# ThermoBot.net
KiCad netlist of a schematic drawn in EAGLE
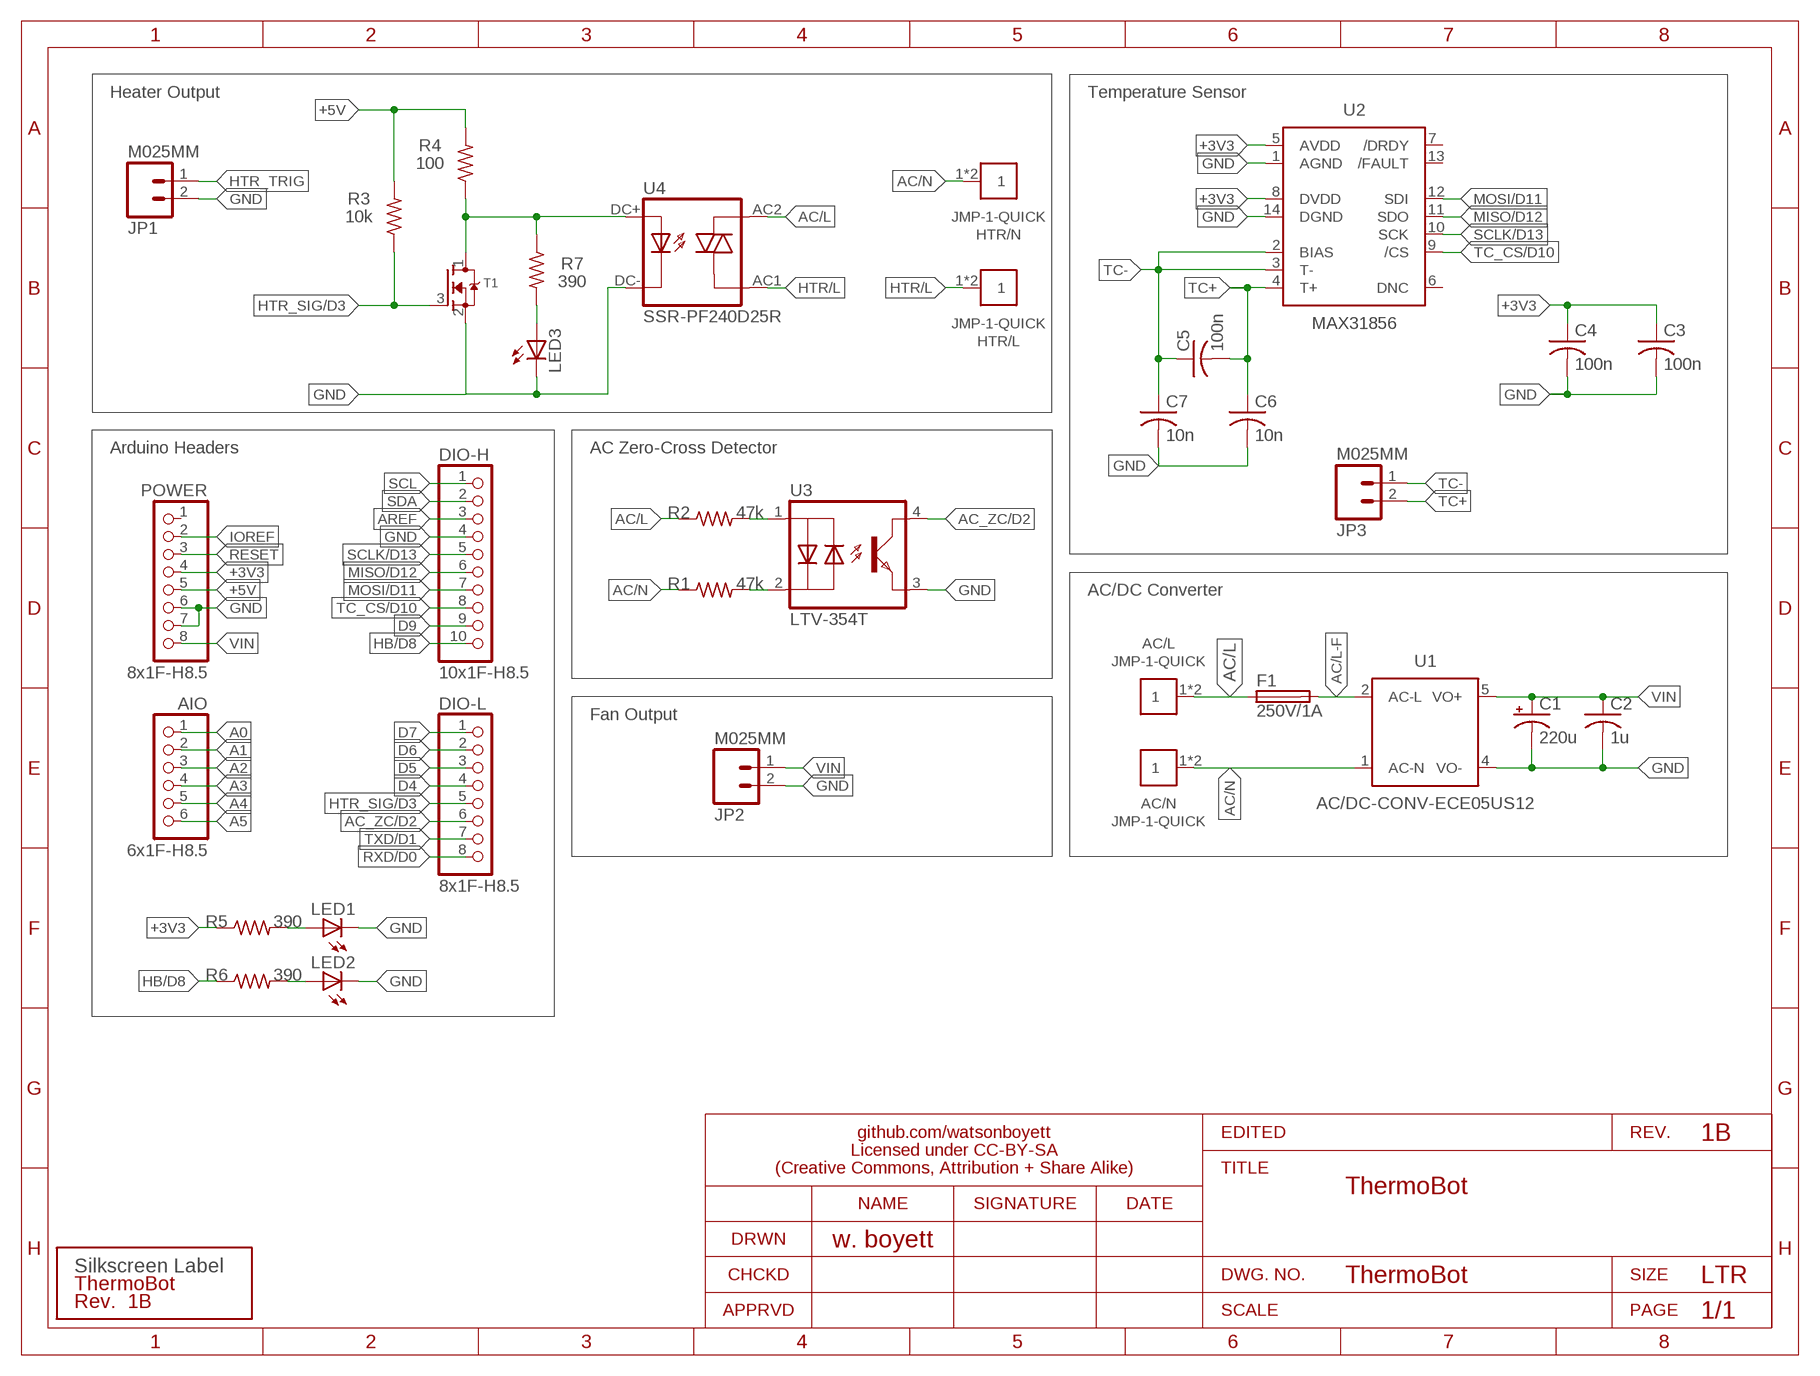
[diagram p0: schematic, sheet 1]

(export (version "E")
  (design (tool "Eeschema 10.0.6"))
  (components
    (comp (ref "AC/L")
      (value "JMP-1-QUICK")
      (footprint "eagle-import:QUICK-1")
      (fields (field (name "MPN") "1287"))
      (libsource (lib "eagle-import") (part "JMP-1-QUICK"))
    )
    (comp (ref "AC/N")
      (value "JMP-1-QUICK")
      (footprint "eagle-import:QUICK-1")
      (fields (field (name "MPN") "1287"))
      (libsource (lib "eagle-import") (part "JMP-1-QUICK"))
    )
    (comp (ref "AIO")
      (value "6x1F-H8.5")
      (footprint "eagle-import:1X06")
      (libsource (lib "eagle-import") (part "PINHD-1X6TH"))
    )
    (comp (ref "C1")
      (value "220u")
      (footprint "eagle-import:153CLV-1014")
      (libsource (lib "eagle-import") (part "CPOL-US153CLV-1014"))
    )
    (comp (ref "C2")
      (value "1u")
      (footprint "eagle-import:C0805")
      (libsource (lib "eagle-import") (part "C-USC0805"))
    )
    (comp (ref "C3")
      (value "100n")
      (footprint "eagle-import:C0805")
      (libsource (lib "eagle-import") (part "C-USC0805"))
    )
    (comp (ref "C4")
      (value "100n")
      (footprint "eagle-import:C0805")
      (libsource (lib "eagle-import") (part "C-USC0805"))
    )
    (comp (ref "C5")
      (value "100n")
      (footprint "eagle-import:C0805")
      (libsource (lib "eagle-import") (part "C-USC0805"))
    )
    (comp (ref "C6")
      (value "10n")
      (footprint "eagle-import:C0805")
      (libsource (lib "eagle-import") (part "C-USC0805"))
    )
    (comp (ref "C7")
      (value "10n")
      (footprint "eagle-import:C0805")
      (libsource (lib "eagle-import") (part "C-USC0805"))
    )
    (comp (ref "DIO-H")
      (value "10x1F-H8.5")
      (footprint "eagle-import:1X10")
      (libsource (lib "eagle-import") (part "PINHD-1X10TH"))
    )
    (comp (ref "DIO-L")
      (value "8x1F-H8.5")
      (footprint "eagle-import:1X08")
      (libsource (lib "eagle-import") (part "PINHD-1X8TH"))
    )
    (comp (ref "F1")
      (value "250V/1A")
      (footprint "eagle-import:2SMD-2410")
      (fields
        (field (name "MPN") "0452004.MRL")
        (field (name "MPN_1") "0454001.MR")
        (field (name "PN-DK") "F3144CT-ND")
      )
      (libsource (lib "eagle-import") (part "FUSE2410"))
    )
    (comp (ref "HTR/L")
      (value "JMP-1-QUICK")
      (footprint "eagle-import:QUICK-1")
      (fields (field (name "MPN") "1287"))
      (libsource (lib "eagle-import") (part "JMP-1-QUICK"))
    )
    (comp (ref "HTR/N")
      (value "JMP-1-QUICK")
      (footprint "eagle-import:QUICK-1")
      (fields (field (name "MPN") "1287"))
      (libsource (lib "eagle-import") (part "JMP-1-QUICK"))
    )
    (comp (ref "JP1")
      (value "M025MM")
      (footprint "eagle-import:SCREWTERMINAL-5MM-2")
      (fields (field (name "MPN") "1729128"))
      (libsource (lib "eagle-import") (part "M025MM"))
    )
    (comp (ref "JP2")
      (value "M025MM")
      (footprint "eagle-import:SCREWTERMINAL-5MM-2")
      (fields (field (name "MPN") "1729128"))
      (libsource (lib "eagle-import") (part "M025MM"))
    )
    (comp (ref "JP3")
      (value "M025MM")
      (footprint "eagle-import:SCREWTERMINAL-5MM-2")
      (fields (field (name "MPN") "1729128"))
      (libsource (lib "eagle-import") (part "M025MM"))
    )
    (comp (ref "LED1")
      (value "LEDCHIP-LED0805")
      (footprint "eagle-import:CHIP-LED0805")
      (fields (field (name "MPN") "SML-LXT0805IW-TR"))
      (libsource (lib "eagle-import") (part "LEDCHIP-LED0805"))
    )
    (comp (ref "LED2")
      (value "LEDCHIP-LED0805")
      (footprint "eagle-import:CHIP-LED0805")
      (fields (field (name "MPN") "SML-LXT0805IW-TR"))
      (libsource (lib "eagle-import") (part "LEDCHIP-LED0805"))
    )
    (comp (ref "LED3")
      (value "LEDCHIP-LED0805")
      (footprint "eagle-import:CHIP-LED0805")
      (fields (field (name "MPN") "SML-LXT0805IW-TR"))
      (libsource (lib "eagle-import") (part "LEDCHIP-LED0805"))
    )
    (comp (ref "POWER")
      (value "8x1F-H8.5")
      (footprint "eagle-import:1X08")
      (libsource (lib "eagle-import") (part "PINHD-1X8TH"))
    )
    (comp (ref "R1")
      (value "47k")
      (footprint "eagle-import:R1206")
      (libsource (lib "eagle-import") (part "R-US_R1206"))
    )
    (comp (ref "R2")
      (value "47k")
      (footprint "eagle-import:R1206")
      (libsource (lib "eagle-import") (part "R-US_R1206"))
    )
    (comp (ref "R3")
      (value "10k")
      (footprint "eagle-import:R0805")
      (libsource (lib "eagle-import") (part "R-US_R0805"))
    )
    (comp (ref "R4")
      (value "100")
      (footprint "eagle-import:R0805")
      (libsource (lib "eagle-import") (part "R-US_R0805"))
    )
    (comp (ref "R5")
      (value "390")
      (footprint "eagle-import:R0805")
      (libsource (lib "eagle-import") (part "R-US_R0805"))
    )
    (comp (ref "R6")
      (value "390")
      (footprint "eagle-import:R0805")
      (libsource (lib "eagle-import") (part "R-US_R0805"))
    )
    (comp (ref "R7")
      (value "390")
      (footprint "eagle-import:R0805")
      (libsource (lib "eagle-import") (part "R-US_R0805"))
    )
    (comp (ref "T1")
      (value "MOSFET-N-SOT23")
      (footprint "eagle-import:SOT-23")
      (libsource (lib "eagle-import") (part "MOSFET-N-SOT23"))
    )
    (comp (ref "U$1")
      (value "SILK_QC")
      (footprint "eagle-import:SILK_QC")
      (fields (field (name "MPN") "DNP") (field (name "PRODUCT") "ThermoBot") (field (name "REV") "1B"))
      (libsource (lib "eagle-import") (part "SILK_QC"))
    )
    (comp (ref "U1")
      (value "AC/DC-CONV-ECE05US12")
      (footprint "eagle-import:ECE05")
      (fields (field (name "MFG") "XP Power") (field (name "MPN") "ECE05US12"))
      (libsource (lib "eagle-import") (part "AC/DC-CONV-ECE05US12"))
    )
    (comp (ref "U2")
      (value "MAX31856")
      (footprint "eagle-import:TSSOP14")
      (fields (field (name "MPN") "MAX31856MUD+"))
      (libsource (lib "eagle-import") (part "MAX31856"))
    )
    (comp (ref "U3")
      (value "LTV-354T")
      (footprint "eagle-import:SOP-4")
      (libsource (lib "eagle-import") (part "LTV-354T"))
    )
    (comp (ref "U4")
      (value "SSR-PF240D25R")
      (footprint "eagle-import:SIP-4")
      (fields (field (name "MFG") "Crydom Co.") (field (name "MPN") "PF240D25R"))
      (libsource (lib "eagle-import") (part "SSR-PF240D25R"))
    )
  )
  (nets
    (net (code "1") (name "+3V3") (class "Default")
      (node (ref "C3") (pin "1") (pinfunction "1_1") (pintype "passive"))
      (node (ref "C4") (pin "1") (pinfunction "1_1") (pintype "passive"))
      (node (ref "POWER") (pin "4") (pinfunction "4_4") (pintype "passive"))
      (node (ref "R5") (pin "1") (pinfunction "1_1") (pintype "passive"))
      (node (ref "U2") (pin "5") (pinfunction "AVDD_5") (pintype "power_in"))
      (node (ref "U2") (pin "8") (pinfunction "DVDD_8") (pintype "power_in"))
    )
    (net (code "2") (name "+5V") (class "Default")
      (node (ref "POWER") (pin "5") (pinfunction "5_5") (pintype "passive"))
      (node (ref "R3") (pin "2") (pinfunction "2_2") (pintype "passive"))
      (node (ref "R4") (pin "2") (pinfunction "2_2") (pintype "passive"))
    )
    (net (code "3") (name "A0") (class "Default")
      (node (ref "AIO") (pin "1") (pinfunction "1_1") (pintype "passive"))
    )
    (net (code "4") (name "A1") (class "Default")
      (node (ref "AIO") (pin "2") (pinfunction "2_2") (pintype "passive"))
    )
    (net (code "5") (name "A2") (class "Default")
      (node (ref "AIO") (pin "3") (pinfunction "3_3") (pintype "passive"))
    )
    (net (code "6") (name "A3") (class "Default")
      (node (ref "AIO") (pin "4") (pinfunction "4_4") (pintype "passive"))
    )
    (net (code "7") (name "A4") (class "Default")
      (node (ref "AIO") (pin "5") (pinfunction "5_5") (pintype "passive"))
    )
    (net (code "8") (name "A5") (class "Default")
      (node (ref "AIO") (pin "6") (pinfunction "6_6") (pintype "passive"))
    )
    (net (code "9") (name "AC_ZC{slash}D2") (class "Default")
      (node (ref "DIO-L") (pin "6") (pinfunction "6_6") (pintype "passive"))
      (node (ref "U3") (pin "4") (pinfunction "COL_4") (pintype "passive"))
    )
    (net (code "10") (name "AC{slash}L") (class "Default")
      (node (ref "AC/L") (pin "1") (pinfunction "1_1") (pintype "bidirectional"))
      (node (ref "AC/L") (pin "2") (pinfunction "1_2") (pintype "bidirectional"))
      (node (ref "F1") (pin "P$1") (pinfunction "1_P$1") (pintype "passive"))
      (node (ref "R2") (pin "1") (pinfunction "1_1") (pintype "passive"))
      (node (ref "U4") (pin "AC2") (pinfunction "A2_AC2") (pintype "passive"))
    )
    (net (code "11") (name "AC{slash}L-F") (class "Default")
      (node (ref "F1") (pin "P$2") (pinfunction "2_P$2") (pintype "passive"))
      (node (ref "U1") (pin "2") (pinfunction "AC-L_2") (pintype "passive"))
    )
    (net (code "12") (name "AC{slash}N") (class "Default")
      (node (ref "AC/N") (pin "1") (pinfunction "1_1") (pintype "bidirectional"))
      (node (ref "AC/N") (pin "2") (pinfunction "1_2") (pintype "bidirectional"))
      (node (ref "HTR/N") (pin "1") (pinfunction "1_1") (pintype "bidirectional"))
      (node (ref "HTR/N") (pin "2") (pinfunction "1_2") (pintype "bidirectional"))
      (node (ref "R1") (pin "1") (pinfunction "1_1") (pintype "passive"))
      (node (ref "U1") (pin "1") (pinfunction "AC-N_1") (pintype "passive"))
    )
    (net (code "13") (name "AREF") (class "Default")
      (node (ref "DIO-H") (pin "3") (pinfunction "3_3") (pintype "passive"))
    )
    (net (code "14") (name "D4") (class "Default")
      (node (ref "DIO-L") (pin "4") (pinfunction "4_4") (pintype "passive"))
    )
    (net (code "15") (name "D5") (class "Default")
      (node (ref "DIO-L") (pin "3") (pinfunction "3_3") (pintype "passive"))
    )
    (net (code "16") (name "D6") (class "Default")
      (node (ref "DIO-L") (pin "2") (pinfunction "2_2") (pintype "passive"))
    )
    (net (code "17") (name "D7") (class "Default")
      (node (ref "DIO-L") (pin "1") (pinfunction "1_1") (pintype "passive"))
    )
    (net (code "18") (name "D9") (class "Default")
      (node (ref "DIO-H") (pin "9") (pinfunction "9_9") (pintype "passive"))
    )
    (net (code "19") (name "GND") (class "Default")
      (node (ref "C1") (pin "-") (pinfunction "-_-") (pintype "passive"))
      (node (ref "C2") (pin "2") (pinfunction "2_2") (pintype "passive"))
      (node (ref "C3") (pin "2") (pinfunction "2_2") (pintype "passive"))
      (node (ref "C4") (pin "2") (pinfunction "2_2") (pintype "passive"))
      (node (ref "C6") (pin "2") (pinfunction "2_2") (pintype "passive"))
      (node (ref "C7") (pin "2") (pinfunction "2_2") (pintype "passive"))
      (node (ref "DIO-H") (pin "4") (pinfunction "4_4") (pintype "passive"))
      (node (ref "JP1") (pin "2") (pinfunction "2_2") (pintype "passive"))
      (node (ref "JP2") (pin "2") (pinfunction "2_2") (pintype "passive"))
      (node (ref "LED1") (pin "C") (pinfunction "C_C") (pintype "passive"))
      (node (ref "LED2") (pin "C") (pinfunction "C_C") (pintype "passive"))
      (node (ref "LED3") (pin "C") (pinfunction "C_C") (pintype "passive"))
      (node (ref "POWER") (pin "6") (pinfunction "6_6") (pintype "passive"))
      (node (ref "POWER") (pin "7") (pinfunction "7_7") (pintype "passive"))
      (node (ref "T1") (pin "2") (pinfunction "S1_2") (pintype "bidirectional"))
      (node (ref "U1") (pin "4") (pinfunction "VO-_4") (pintype "passive"))
      (node (ref "U2") (pin "1") (pinfunction "AGND_1") (pintype "power_in"))
      (node (ref "U2") (pin "14") (pinfunction "DGND_14") (pintype "power_in"))
      (node (ref "U3") (pin "3") (pinfunction "EMIT_3") (pintype "passive"))
      (node (ref "U4") (pin "DC-") (pinfunction "C_DC-") (pintype "passive"))
    )
    (net (code "20") (name "HB{slash}D8") (class "Default")
      (node (ref "DIO-H") (pin "10") (pinfunction "10_10") (pintype "passive"))
      (node (ref "R6") (pin "1") (pinfunction "1_1") (pintype "passive"))
    )
    (net (code "21") (name "HTR_SIG{slash}D3") (class "Default")
      (node (ref "DIO-L") (pin "5") (pinfunction "5_5") (pintype "passive"))
      (node (ref "R3") (pin "1") (pinfunction "1_1") (pintype "passive"))
      (node (ref "T1") (pin "3") (pinfunction "G1_3") (pintype "bidirectional"))
    )
    (net (code "22") (name "HTR_TRIG") (class "Default")
      (node (ref "JP1") (pin "1") (pinfunction "1_1") (pintype "passive"))
      (node (ref "R4") (pin "1") (pinfunction "1_1") (pintype "passive"))
      (node (ref "R7") (pin "1") (pinfunction "1_1") (pintype "passive"))
      (node (ref "T1") (pin "1") (pinfunction "D1_1") (pintype "bidirectional"))
      (node (ref "U4") (pin "DC+") (pinfunction "A_DC+") (pintype "passive"))
    )
    (net (code "23") (name "HTR{slash}L") (class "Default")
      (node (ref "HTR/L") (pin "1") (pinfunction "1_1") (pintype "bidirectional"))
      (node (ref "HTR/L") (pin "2") (pinfunction "1_2") (pintype "bidirectional"))
      (node (ref "U4") (pin "AC1") (pinfunction "A1_AC1") (pintype "passive"))
    )
    (net (code "24") (name "IOREF") (class "Default")
      (node (ref "POWER") (pin "2") (pinfunction "2_2") (pintype "passive"))
    )
    (net (code "25") (name "MISO{slash}D12") (class "Default")
      (node (ref "DIO-H") (pin "6") (pinfunction "6_6") (pintype "passive"))
      (node (ref "U2") (pin "11") (pinfunction "SDO_11") (pintype "bidirectional"))
    )
    (net (code "26") (name "MOSI{slash}D11") (class "Default")
      (node (ref "DIO-H") (pin "7") (pinfunction "7_7") (pintype "passive"))
      (node (ref "U2") (pin "12") (pinfunction "SDI_12") (pintype "bidirectional"))
    )
    (net (code "27") (name "Net-(LED1-PadA)") (class "Default")
      (node (ref "LED1") (pin "A") (pinfunction "A_A") (pintype "passive"))
      (node (ref "R5") (pin "2") (pinfunction "2_2") (pintype "passive"))
    )
    (net (code "28") (name "Net-(LED2-PadA)") (class "Default")
      (node (ref "LED2") (pin "A") (pinfunction "A_A") (pintype "passive"))
      (node (ref "R6") (pin "2") (pinfunction "2_2") (pintype "passive"))
    )
    (net (code "29") (name "Net-(LED3-PadA)") (class "Default")
      (node (ref "LED3") (pin "A") (pinfunction "A_A") (pintype "passive"))
      (node (ref "R7") (pin "2") (pinfunction "2_2") (pintype "passive"))
    )
    (net (code "30") (name "Net-(U3-A)") (class "Default")
      (node (ref "R2") (pin "2") (pinfunction "2_2") (pintype "passive"))
      (node (ref "U3") (pin "1") (pinfunction "A_1") (pintype "passive"))
    )
    (net (code "31") (name "Net-(U3-C)") (class "Default")
      (node (ref "R1") (pin "2") (pinfunction "2_2") (pintype "passive"))
      (node (ref "U3") (pin "2") (pinfunction "C_2") (pintype "passive"))
    )
    (net (code "32") (name "RESET") (class "Default")
      (node (ref "POWER") (pin "3") (pinfunction "3_3") (pintype "passive"))
    )
    (net (code "33") (name "RXD{slash}D0") (class "Default")
      (node (ref "DIO-L") (pin "8") (pinfunction "8_8") (pintype "passive"))
    )
    (net (code "34") (name "SCL") (class "Default")
      (node (ref "DIO-H") (pin "1") (pinfunction "1_1") (pintype "passive"))
    )
    (net (code "35") (name "SCLK{slash}D13") (class "Default")
      (node (ref "DIO-H") (pin "5") (pinfunction "5_5") (pintype "passive"))
      (node (ref "U2") (pin "10") (pinfunction "SCK_10") (pintype "bidirectional"))
    )
    (net (code "36") (name "SDA") (class "Default")
      (node (ref "DIO-H") (pin "2") (pinfunction "2_2") (pintype "passive"))
    )
    (net (code "37") (name "TC+") (class "Default")
      (node (ref "C5") (pin "2") (pinfunction "2_2") (pintype "passive"))
      (node (ref "C6") (pin "1") (pinfunction "1_1") (pintype "passive"))
      (node (ref "JP3") (pin "2") (pinfunction "2_2") (pintype "passive"))
      (node (ref "U2") (pin "4") (pinfunction "T+_4") (pintype "bidirectional"))
    )
    (net (code "38") (name "TC-") (class "Default")
      (node (ref "C5") (pin "1") (pinfunction "1_1") (pintype "passive"))
      (node (ref "C7") (pin "1") (pinfunction "1_1") (pintype "passive"))
      (node (ref "JP3") (pin "1") (pinfunction "1_1") (pintype "passive"))
      (node (ref "U2") (pin "2") (pinfunction "BIAS_2") (pintype "bidirectional"))
      (node (ref "U2") (pin "3") (pinfunction "T-_3") (pintype "bidirectional"))
    )
    (net (code "39") (name "TC_CS{slash}D10") (class "Default")
      (node (ref "DIO-H") (pin "8") (pinfunction "8_8") (pintype "passive"))
      (node (ref "U2") (pin "9") (pinfunction "/CS_9") (pintype "bidirectional"))
    )
    (net (code "40") (name "TXD{slash}D1") (class "Default")
      (node (ref "DIO-L") (pin "7") (pinfunction "7_7") (pintype "passive"))
    )
    (net (code "41") (name "VIN") (class "Default")
      (node (ref "C1") (pin "+") (pinfunction "+_+") (pintype "passive"))
      (node (ref "C2") (pin "1") (pinfunction "1_1") (pintype "passive"))
      (node (ref "JP2") (pin "1") (pinfunction "1_1") (pintype "passive"))
      (node (ref "POWER") (pin "8") (pinfunction "8_8") (pintype "passive"))
      (node (ref "U1") (pin "5") (pinfunction "VO+_5") (pintype "passive"))
    )
    (net (code "42") (name "unconnected-(POWER-Pad1)") (class "Default")
      (node (ref "POWER") (pin "1") (pinfunction "1_1") (pintype "passive"))
    )
    (net (code "43") (name "unconnected-(U2-DNC-Pad6)") (class "Default")
      (node (ref "U2") (pin "6") (pinfunction "DNC_6") (pintype "no_connect"))
    )
    (net (code "44") (name "unconnected-(U2-{slash}DRDY-Pad7)") (class "Default")
      (node (ref "U2") (pin "7") (pinfunction "/DRDY_7") (pintype "bidirectional"))
    )
    (net (code "45") (name "unconnected-(U2-{slash}FAULT-Pad13)") (class "Default")
      (node (ref "U2") (pin "13") (pinfunction "/FAULT_13") (pintype "bidirectional"))
    )
  )
)
